# windidr.net
KiCad netlist of a schematic drawn in EAGLE
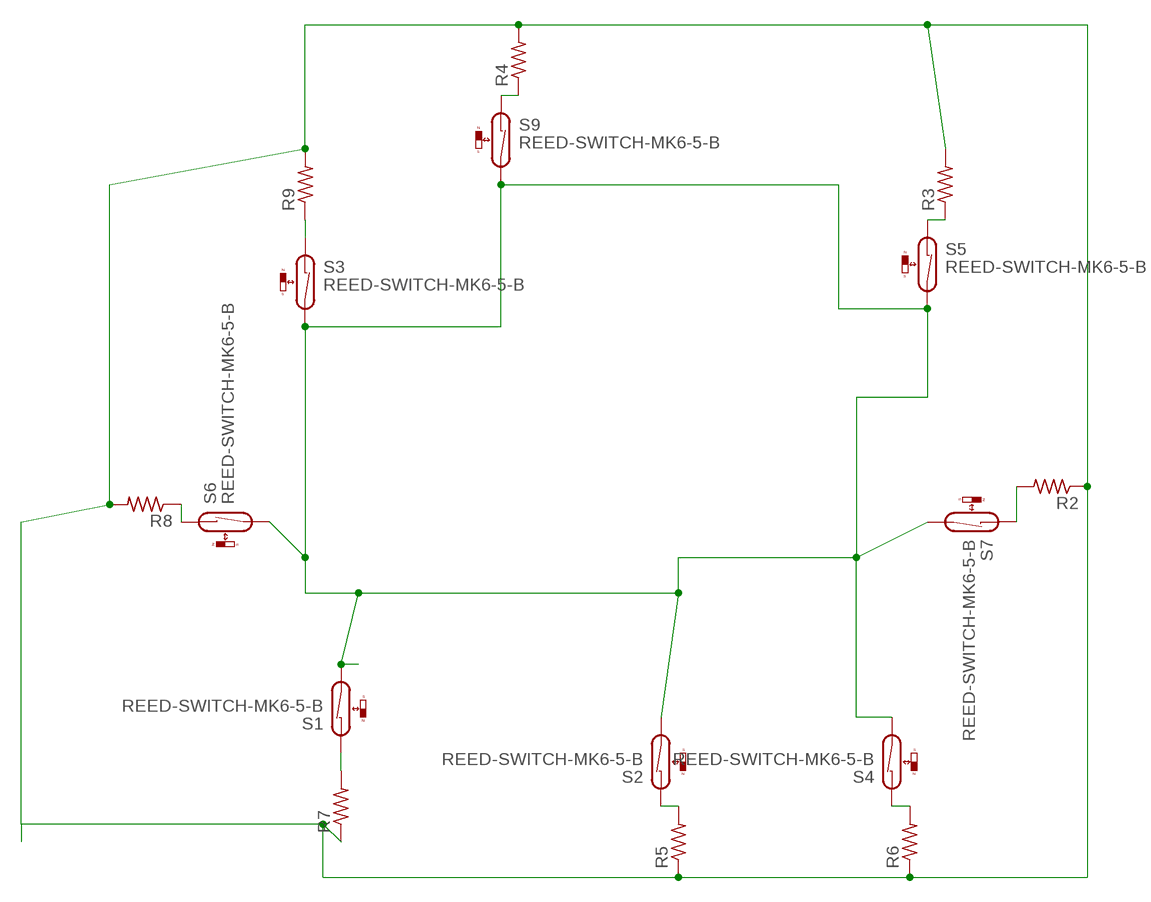
[diagram p0: schematic, sheet 1]

(export (version "E")
  (design (tool "Eeschema 10.0.6"))
  (components
    (comp (ref "R2")
      (value "R-US_0309/10")
      (footprint "eagle-import:0309_10")
      (libsource (lib "eagle-import") (part "R-US_0309/10"))
    )
    (comp (ref "R3")
      (value "R-US_0309/10")
      (footprint "eagle-import:0309_10")
      (libsource (lib "eagle-import") (part "R-US_0309/10"))
    )
    (comp (ref "R4")
      (value "R-US_0309/10")
      (footprint "eagle-import:0309_10")
      (libsource (lib "eagle-import") (part "R-US_0309/10"))
    )
    (comp (ref "R5")
      (value "R-US_0309/10")
      (footprint "eagle-import:0309_10")
      (libsource (lib "eagle-import") (part "R-US_0309/10"))
    )
    (comp (ref "R6")
      (value "R-US_0309/10")
      (footprint "eagle-import:0309_10")
      (libsource (lib "eagle-import") (part "R-US_0309/10"))
    )
    (comp (ref "R7")
      (value "R-US_0309/10")
      (footprint "eagle-import:0309_10")
      (libsource (lib "eagle-import") (part "R-US_0309/10"))
    )
    (comp (ref "R8")
      (value "R-US_0309/10")
      (footprint "eagle-import:0309_10")
      (libsource (lib "eagle-import") (part "R-US_0309/10"))
    )
    (comp (ref "R9")
      (value "R-US_0309/10")
      (footprint "eagle-import:0309_10")
      (libsource (lib "eagle-import") (part "R-US_0309/10"))
    )
    (comp (ref "S1")
      (value "REED-SWITCH-MK6-5-B")
      (footprint "eagle-import:MK6-5")
      (fields (field (name "MF") "MEDER") (field (name "MPN") "MK6-5-B"))
      (libsource (lib "eagle-import") (part "REED-SWITCH-MK6-5-B"))
    )
    (comp (ref "S2")
      (value "REED-SWITCH-MK6-5-B")
      (footprint "eagle-import:MK6-5")
      (fields (field (name "MF") "MEDER") (field (name "MPN") "MK6-5-B"))
      (libsource (lib "eagle-import") (part "REED-SWITCH-MK6-5-B"))
    )
    (comp (ref "S3")
      (value "REED-SWITCH-MK6-5-B")
      (footprint "eagle-import:MK6-5")
      (fields (field (name "MF") "MEDER") (field (name "MPN") "MK6-5-B"))
      (libsource (lib "eagle-import") (part "REED-SWITCH-MK6-5-B"))
    )
    (comp (ref "S4")
      (value "REED-SWITCH-MK6-5-B")
      (footprint "eagle-import:MK6-5")
      (fields (field (name "MF") "MEDER") (field (name "MPN") "MK6-5-B"))
      (libsource (lib "eagle-import") (part "REED-SWITCH-MK6-5-B"))
    )
    (comp (ref "S5")
      (value "REED-SWITCH-MK6-5-B")
      (footprint "eagle-import:MK6-5")
      (fields (field (name "MF") "MEDER") (field (name "MPN") "MK6-5-B"))
      (libsource (lib "eagle-import") (part "REED-SWITCH-MK6-5-B"))
    )
    (comp (ref "S6")
      (value "REED-SWITCH-MK6-5-B")
      (footprint "eagle-import:MK6-5")
      (fields (field (name "MF") "MEDER") (field (name "MPN") "MK6-5-B"))
      (libsource (lib "eagle-import") (part "REED-SWITCH-MK6-5-B"))
    )
    (comp (ref "S7")
      (value "REED-SWITCH-MK6-5-B")
      (footprint "eagle-import:MK6-5")
      (fields (field (name "MF") "MEDER") (field (name "MPN") "MK6-5-B"))
      (libsource (lib "eagle-import") (part "REED-SWITCH-MK6-5-B"))
    )
    (comp (ref "S9")
      (value "REED-SWITCH-MK6-5-B")
      (footprint "eagle-import:MK6-5")
      (fields (field (name "MF") "MEDER") (field (name "MPN") "MK6-5-B"))
      (libsource (lib "eagle-import") (part "REED-SWITCH-MK6-5-B"))
    )
  )
  (nets
    (net (code "1") (name "Net-(R2-Pad1)") (class "Default")
      (node (ref "R2") (pin "1") (pinfunction "1_1") (pintype "passive"))
      (node (ref "R3") (pin "2") (pinfunction "2_2") (pintype "passive"))
      (node (ref "R4") (pin "2") (pinfunction "2_2") (pintype "passive"))
      (node (ref "R5") (pin "1") (pinfunction "1_1") (pintype "passive"))
      (node (ref "R6") (pin "1") (pinfunction "1_1") (pintype "passive"))
      (node (ref "R7") (pin "1") (pinfunction "1_1") (pintype "passive"))
      (node (ref "R8") (pin "2") (pinfunction "2_2") (pintype "passive"))
      (node (ref "R9") (pin "2") (pinfunction "2_2") (pintype "passive"))
    )
    (net (code "2") (name "Net-(R2-Pad2)") (class "Default")
      (node (ref "R2") (pin "2") (pinfunction "2_2") (pintype "passive"))
      (node (ref "S7") (pin "1") (pinfunction "1_1") (pintype "passive"))
    )
    (net (code "3") (name "Net-(R3-Pad1)") (class "Default")
      (node (ref "R3") (pin "1") (pinfunction "1_1") (pintype "passive"))
      (node (ref "S5") (pin "1") (pinfunction "1_1") (pintype "passive"))
    )
    (net (code "4") (name "Net-(R4-Pad1)") (class "Default")
      (node (ref "R4") (pin "1") (pinfunction "1_1") (pintype "passive"))
      (node (ref "S9") (pin "1") (pinfunction "1_1") (pintype "passive"))
    )
    (net (code "5") (name "Net-(R5-Pad2)") (class "Default")
      (node (ref "R5") (pin "2") (pinfunction "2_2") (pintype "passive"))
      (node (ref "S2") (pin "1") (pinfunction "1_1") (pintype "passive"))
    )
    (net (code "6") (name "Net-(R6-Pad2)") (class "Default")
      (node (ref "R6") (pin "2") (pinfunction "2_2") (pintype "passive"))
      (node (ref "S4") (pin "1") (pinfunction "1_1") (pintype "passive"))
    )
    (net (code "7") (name "Net-(R7-Pad2)") (class "Default")
      (node (ref "R7") (pin "2") (pinfunction "2_2") (pintype "passive"))
      (node (ref "S1") (pin "1") (pinfunction "1_1") (pintype "passive"))
    )
    (net (code "8") (name "Net-(R8-Pad1)") (class "Default")
      (node (ref "R8") (pin "1") (pinfunction "1_1") (pintype "passive"))
      (node (ref "S6") (pin "1") (pinfunction "1_1") (pintype "passive"))
    )
    (net (code "9") (name "Net-(R9-Pad1)") (class "Default")
      (node (ref "R9") (pin "1") (pinfunction "1_1") (pintype "passive"))
      (node (ref "S3") (pin "1") (pinfunction "1_1") (pintype "passive"))
    )
    (net (code "10") (name "Net-(S1-Pad2)") (class "Default")
      (node (ref "S1") (pin "2") (pinfunction "2_2") (pintype "passive"))
      (node (ref "S2") (pin "2") (pinfunction "2_2") (pintype "passive"))
      (node (ref "S3") (pin "2") (pinfunction "2_2") (pintype "passive"))
      (node (ref "S4") (pin "2") (pinfunction "2_2") (pintype "passive"))
      (node (ref "S5") (pin "2") (pinfunction "2_2") (pintype "passive"))
      (node (ref "S6") (pin "2") (pinfunction "2_2") (pintype "passive"))
      (node (ref "S7") (pin "2") (pinfunction "2_2") (pintype "passive"))
      (node (ref "S9") (pin "2") (pinfunction "2_2") (pintype "passive"))
    )
  )
)
